# U_I_Meter_Bottom.net
KiCad netlist of a schematic drawn in Altium Designer
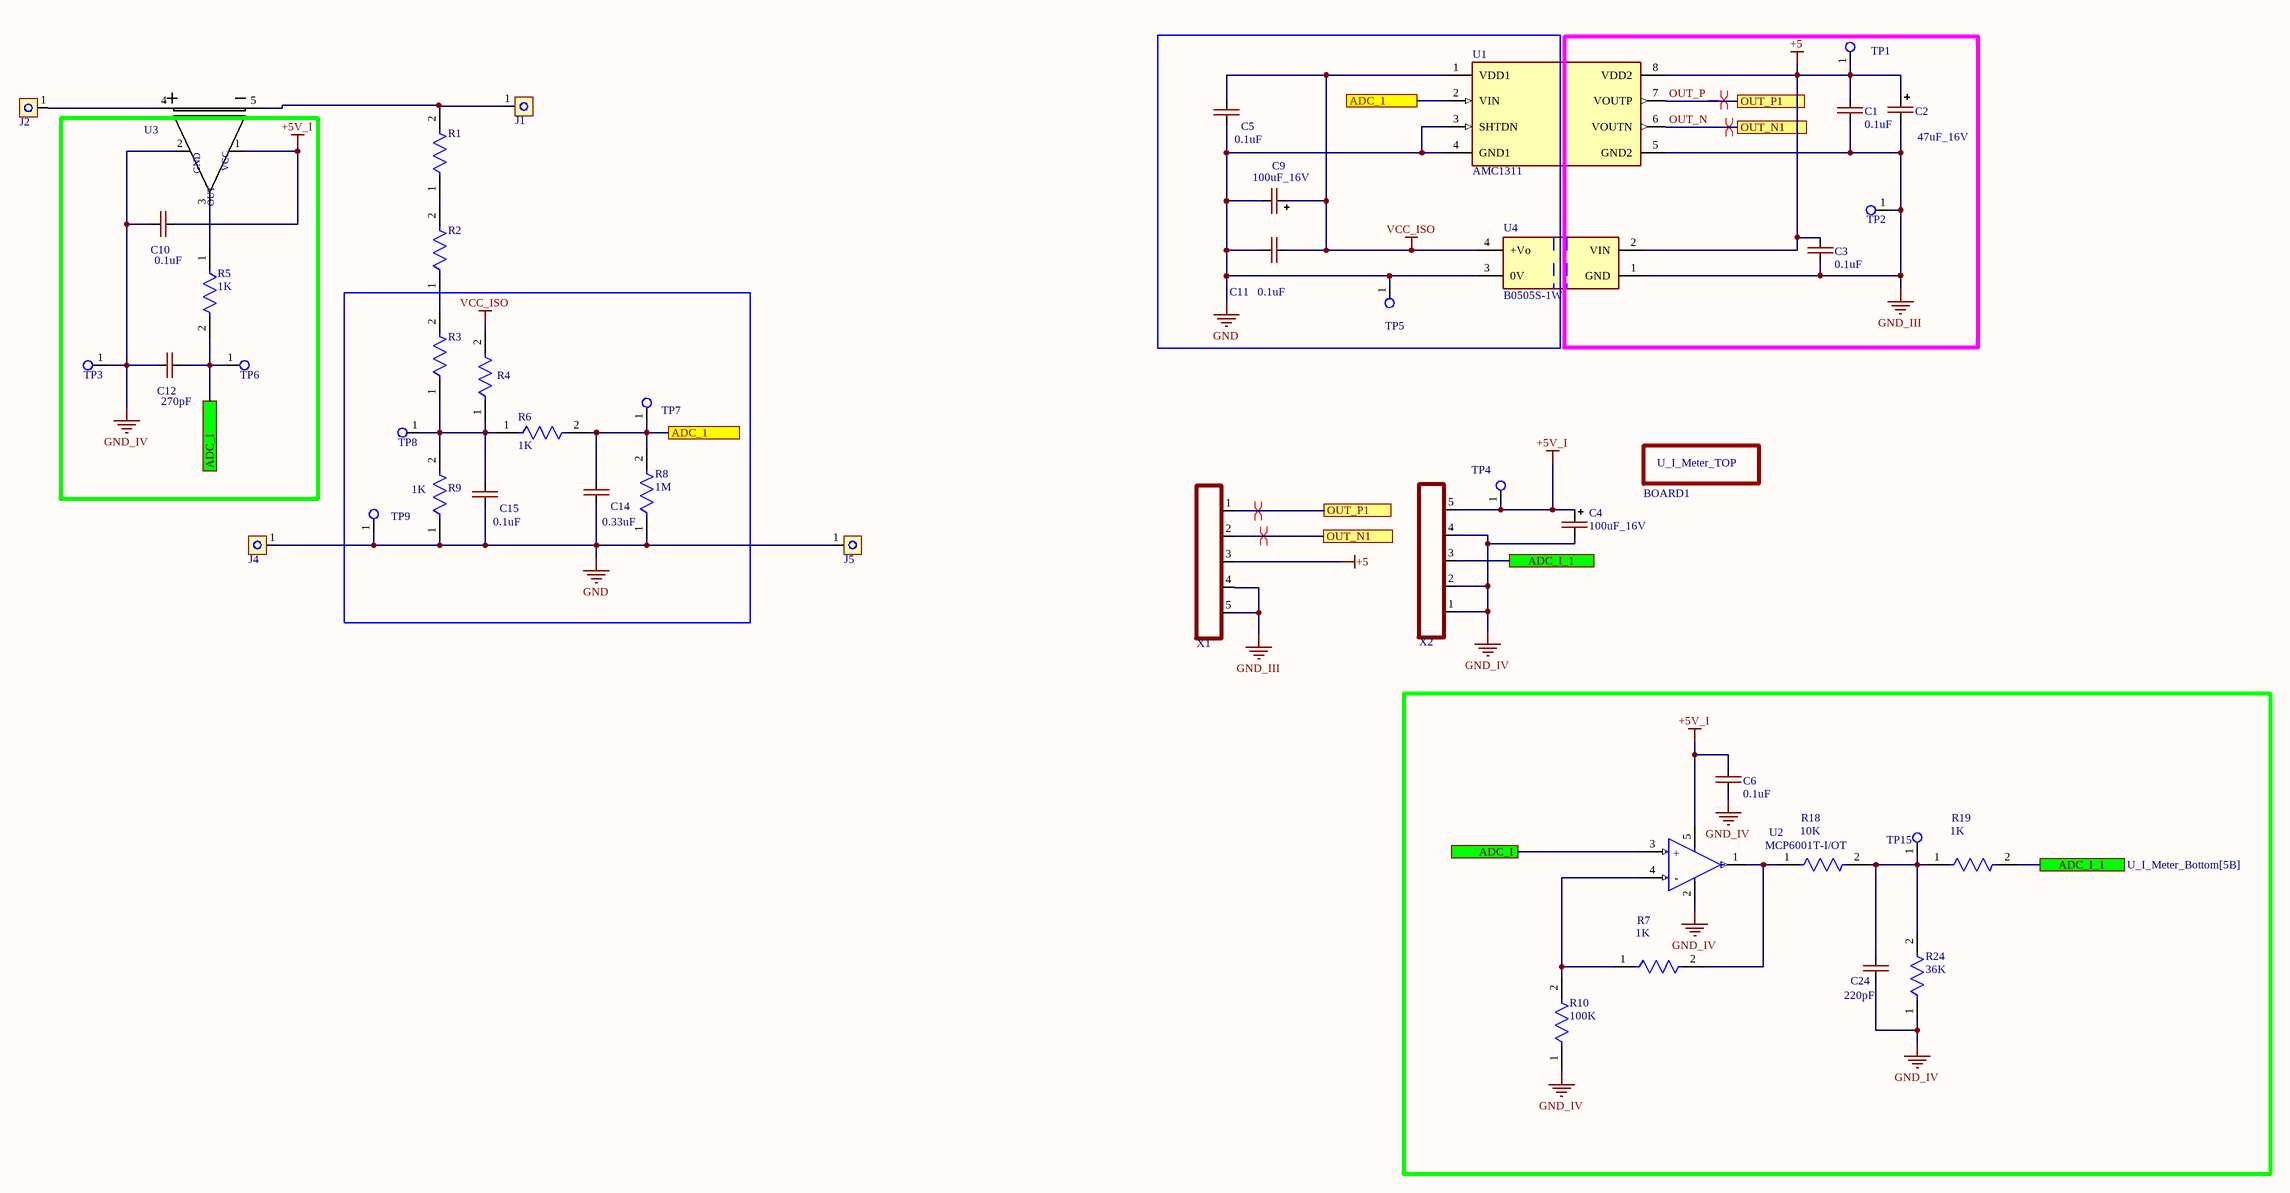
[diagram p0: U_I_Meter_Bottom.SchDoc]

(export (version "E")
  (design (tool "Eeschema 10.0.6"))
  (components
    (comp (ref "BOARD1")
      (value "U_I_Meter_TOP")
      (footprint "U_I_Meter_TOP")
      (libsource (lib "U_I_Meter_TOP") (part "U_I_Meter_TOP"))
    )
    (comp (ref "C1")
      (value "0.1uF")
      (footprint "CAP-0805")
      (libsource (lib "PASSIVE_COMPONENTS") (part "CAP-NON-POLAR"))
    )
    (comp (ref "C2")
      (value "47uF_16V")
      (footprint "CAP-TAN-D")
      (libsource (lib "PASSIVE_COMPONENTS") (part "CAP-POLAR"))
    )
    (comp (ref "C3")
      (value "0.1uF")
      (footprint "CAP-0805")
      (libsource (lib "PASSIVE_COMPONENTS") (part "CAP-NON-POLAR"))
    )
    (comp (ref "C4")
      (value "100uF_16V")
      (footprint "CAP-TAN-D")
      (libsource (lib "PASSIVE_COMPONENTS") (part "CAP_POL_SMD"))
    )
    (comp (ref "C5")
      (value "0.1uF")
      (footprint "CAP-0805")
      (libsource (lib "PASSIVE_COMPONENTS") (part "CAP-NON-POLAR"))
    )
    (comp (ref "C6")
      (value "0.1uF")
      (footprint "CAP-0805")
      (libsource (lib "PASSIVE_COMPONENTS") (part "CAP-NON-POLAR"))
    )
    (comp (ref "C9")
      (value "100uF_16V")
      (footprint "CAP-TAN-D")
      (libsource (lib "PASSIVE_COMPONENTS") (part "CAP_POL_SMD"))
    )
    (comp (ref "C10")
      (value "0.1uF")
      (footprint "CAP-0805")
      (libsource (lib "PASSIVE_COMPONENTS") (part "CAP-NON-POLAR"))
    )
    (comp (ref "C11")
      (value "0.1uF")
      (footprint "CAP-0805")
      (libsource (lib "PASSIVE_COMPONENTS") (part "CAP-NON-POLAR"))
    )
    (comp (ref "C12")
      (value "270pF")
      (footprint "CAP-0805")
      (libsource (lib "PASSIVE_COMPONENTS") (part "CAP-NON-POLAR"))
    )
    (comp (ref "C14")
      (value "0.33uF")
      (footprint "CAP-0805")
      (libsource (lib "PASSIVE_COMPONENTS") (part "CAP-NON-POLAR"))
    )
    (comp (ref "C15")
      (value "0.1uF")
      (footprint "CAP-0805")
      (libsource (lib "PASSIVE_COMPONENTS") (part "CAP-NON-POLAR"))
    )
    (comp (ref "C24")
      (value "220pF")
      (footprint "CAP-0805")
      (libsource (lib "PASSIVE_COMPONENTS") (part "CAP-NON-POLAR"))
    )
    (comp (ref "J1")
      (value "MG_136_HT")
      (footprint "Conn_MEIGAN_MG136HT")
      (libsource (lib "Connectors") (part "Connector_MEIGAN_MG136HT"))
    )
    (comp (ref "J2")
      (value "MG_136_HT")
      (footprint "Conn_MEIGAN_MG136HT")
      (libsource (lib "") (part "Connector_MEIGAN_MG136HT_1"))
    )
    (comp (ref "J4")
      (value "MG_136_HT")
      (footprint "Conn_MEIGAN_MG136HT")
      (libsource (lib "") (part "Connector_MEIGAN_MG136HT_1"))
    )
    (comp (ref "J5")
      (value "MG_136_HT")
      (footprint "Conn_MEIGAN_MG136HT")
      (libsource (lib "Connectors") (part "Connector_MEIGAN_MG136HT"))
    )
    (comp (ref "R1")
      (value "~")
      (footprint "RES-2512")
      (libsource (lib "PASSIVE_COMPONENTS") (part "RES-CONST"))
    )
    (comp (ref "R2")
      (value "~")
      (footprint "RES-2512")
      (libsource (lib "PASSIVE_COMPONENTS") (part "RES-CONST"))
    )
    (comp (ref "R3")
      (value "~")
      (footprint "RES-2512")
      (libsource (lib "PASSIVE_COMPONENTS") (part "RES-CONST"))
    )
    (comp (ref "R4")
      (value "~")
      (footprint "RES-0805")
      (libsource (lib "PASSIVE_COMPONENTS") (part "RES-CONST"))
    )
    (comp (ref "R5")
      (value "1K")
      (footprint "RES-0805")
      (libsource (lib "PASSIVE_COMPONENTS") (part "RES-CONST"))
    )
    (comp (ref "R6")
      (value "1K")
      (footprint "RES-0805")
      (libsource (lib "PASSIVE_COMPONENTS") (part "RES-CONST"))
    )
    (comp (ref "R7")
      (value "1K")
      (footprint "RES-0805")
      (description "10K")
      (libsource (lib "PASSIVE_COMPONENTS") (part "RES-CONST"))
    )
    (comp (ref "R8")
      (value "1M")
      (footprint "RES-0805")
      (libsource (lib "PASSIVE_COMPONENTS") (part "RES-CONST"))
    )
    (comp (ref "R9")
      (value "1K")
      (footprint "RES_SMD_1210_IPC_B")
      (libsource (lib "PASSIVE_COMPONENTS") (part "RES_1210"))
    )
    (comp (ref "R10")
      (value "100K")
      (footprint "RES-0805")
      (libsource (lib "PASSIVE_COMPONENTS") (part "RES-CONST"))
    )
    (comp (ref "R18")
      (value "10K")
      (footprint "RES-0805")
      (libsource (lib "PASSIVE_COMPONENTS") (part "RES-CONST"))
    )
    (comp (ref "R19")
      (value "1K")
      (footprint "RES-0805")
      (description "10K")
      (libsource (lib "PASSIVE_COMPONENTS") (part "RES-CONST"))
    )
    (comp (ref "R24")
      (value "36K")
      (footprint "RES-0805")
      (libsource (lib "PASSIVE_COMPONENTS") (part "RES-CONST"))
    )
    (comp (ref "TP1")
      (value "Test_Point_PCB")
      (footprint "Test_Point")
      (description "Test_Point")
      (libsource (lib "Connectors") (part "TP_PCB?"))
    )
    (comp (ref "TP2")
      (value "Test_Point_PCB")
      (footprint "Test_Point")
      (description "Test_Point")
      (libsource (lib "Connectors") (part "TP_PCB?"))
    )
    (comp (ref "TP3")
      (value "Test_Point_PCB")
      (footprint "Test_Point")
      (description "Test_Point")
      (libsource (lib "Connectors") (part "TP_PCB?"))
    )
    (comp (ref "TP4")
      (value "Test_Point_PCB")
      (footprint "Test_Point")
      (description "Test_Point")
      (libsource (lib "Connectors") (part "TP_PCB?"))
    )
    (comp (ref "TP5")
      (value "Test_Point_PCB")
      (footprint "Pin_Test_Point(Pink)")
      (description "Test_Point")
      (libsource (lib "Connectors") (part "TP_PCB?"))
    )
    (comp (ref "TP6")
      (value "Test_Point_PCB")
      (footprint "Test_Point")
      (description "Test_Point")
      (libsource (lib "Connectors") (part "TP_PCB?"))
    )
    (comp (ref "TP7")
      (value "Test_Point_PCB")
      (footprint "Test_Point")
      (description "Test_Point")
      (libsource (lib "Connectors") (part "TP_PCB?"))
    )
    (comp (ref "TP8")
      (value "Test_Point_PCB")
      (footprint "Test_Point")
      (description "Test_Point")
      (libsource (lib "Connectors") (part "TP_PCB?"))
    )
    (comp (ref "TP9")
      (value "Test_Point_PCB")
      (footprint "Test_Point")
      (description "Test_Point")
      (libsource (lib "Connectors") (part "TP_PCB?"))
    )
    (comp (ref "TP15")
      (value "Test_Point_PCB")
      (footprint "Test_Point")
      (description "Test_Point")
      (libsource (lib "Connectors") (part "TP_PCB?"))
    )
    (comp (ref "U1")
      (value "AMC1311")
      (footprint "FP-DWV0008A-MFG")
      (libsource (lib "Integrated_Circuts") (part "AMC1311"))
    )
    (comp (ref "U2")
      (value "MCP6001T-I/OT")
      (footprint "SOT-23-5")
      (description "IC OPAMP GP 1 CIRCUIT SOT23-5")
      (fields (field (name "VOLTAGE") "6V"))
      (libsource (lib "Integrated_Circuts") (part "MCP6001T"))
    )
    (comp (ref "U3")
      (value "ACS758")
      (footprint "ACS758-100")
      (libsource (lib "Integrated_Circuts") (part "ACS758"))
    )
    (comp (ref "U4")
      (value "B0505S-1W")
      (footprint "B0505S-1W")
      (libsource (lib "Integrated_Circuts") (part "B0505S-1W"))
    )
    (comp (ref "X1")
      (value "CONN-5-PIN")
      (footprint "CONN-PLS-5-2.54mm")
      (libsource (lib "") (part "CONN-5-PIN_1"))
    )
    (comp (ref "X2")
      (value "CONN-5-PIN")
      (footprint "CONN-PLS-5-2.54mm")
      (libsource (lib "PLS-5__") (part "CONN-5-PIN"))
    )
  )
  (nets
    (net (code "1") (name "+5") (class "Default")
      (node (ref "C1") (pin "1") (pinfunction "1_1") (pintype "passive"))
      (node (ref "C2") (pin "1") (pinfunction "+_1") (pintype "passive"))
      (node (ref "C3") (pin "1") (pinfunction "1_1") (pintype "passive"))
      (node (ref "TP1") (pin "1") (pinfunction "G9_1") (pintype "passive"))
      (node (ref "U1") (pin "8") (pinfunction "VDD2_8") (pintype "power_in"))
      (node (ref "U4") (pin "2") (pinfunction "VIN_2") (pintype "power_in"))
      (node (ref "X1") (pin "3") (pinfunction "3_3") (pintype "passive"))
    )
    (net (code "2") (name "+5V_I") (class "Default")
      (node (ref "C10") (pin "2") (pinfunction "2_2") (pintype "passive"))
      (node (ref "C4") (pin "1") (pinfunction "+_1") (pintype "passive"))
      (node (ref "C6") (pin "2") (pinfunction "2_2") (pintype "passive"))
      (node (ref "TP4") (pin "1") (pinfunction "G9_1") (pintype "passive"))
      (node (ref "U2") (pin "5") (pinfunction "VDD_5") (pintype "power_in"))
      (node (ref "U3") (pin "1") (pinfunction "+VCC_1") (pintype "passive"))
      (node (ref "X2") (pin "5") (pinfunction "5_5") (pintype "passive"))
    )
    (net (code "3") (name "/ADC_1") (class "Default")
      (node (ref "C14") (pin "2") (pinfunction "2_2") (pintype "passive"))
      (node (ref "R6") (pin "2") (pinfunction "2_2") (pintype "passive"))
      (node (ref "R8") (pin "2") (pinfunction "2_2") (pintype "passive"))
      (node (ref "TP7") (pin "1") (pinfunction "G9_1") (pintype "passive"))
      (node (ref "U1") (pin "2") (pinfunction "VIN_2") (pintype "input"))
    )
    (net (code "4") (name "/ADC_I") (class "Default")
      (node (ref "C12") (pin "2") (pinfunction "2_2") (pintype "passive"))
      (node (ref "R5") (pin "2") (pinfunction "2_2") (pintype "passive"))
      (node (ref "TP6") (pin "1") (pinfunction "G9_1") (pintype "passive"))
      (node (ref "U2") (pin "3") (pinfunction "VIN+_3") (pintype "input"))
    )
    (net (code "5") (name "/ADC_I_1") (class "Default")
      (node (ref "R19") (pin "2") (pinfunction "2_2") (pintype "passive"))
      (node (ref "X2") (pin "3") (pinfunction "3_3") (pintype "passive"))
    )
    (net (code "6") (name "/OUT_N") (class "Default")
      (node (ref "U1") (pin "6") (pinfunction "VOUTN_6") (pintype "output"))
      (node (ref "X1") (pin "2") (pinfunction "2_2") (pintype "passive"))
    )
    (net (code "7") (name "/OUT_P") (class "Default")
      (node (ref "U1") (pin "7") (pinfunction "VOUTP_7") (pintype "output"))
      (node (ref "X1") (pin "1") (pinfunction "1_1") (pintype "passive"))
    )
    (net (code "8") (name "GND") (class "Default")
      (node (ref "C11") (pin "2") (pinfunction "2_2") (pintype "passive"))
      (node (ref "C14") (pin "1") (pinfunction "1_1") (pintype "passive"))
      (node (ref "C15") (pin "1") (pinfunction "1_1") (pintype "passive"))
      (node (ref "C5") (pin "1") (pinfunction "1_1") (pintype "passive"))
      (node (ref "C9") (pin "2") (pinfunction "-_2") (pintype "passive"))
      (node (ref "J4") (pin "1") (pinfunction "17_1") (pintype "passive"))
      (node (ref "J5") (pin "1") (pinfunction "17_1") (pintype "passive"))
      (node (ref "R8") (pin "1") (pinfunction "1_1") (pintype "passive"))
      (node (ref "R9") (pin "1") (pinfunction "1_1") (pintype "passive"))
      (node (ref "TP5") (pin "1") (pinfunction "G9_1") (pintype "passive"))
      (node (ref "TP9") (pin "1") (pinfunction "G9_1") (pintype "passive"))
      (node (ref "U1") (pin "3") (pinfunction "SHTDN_3") (pintype "input"))
      (node (ref "U1") (pin "4") (pinfunction "GND1_4") (pintype "power_in"))
      (node (ref "U4") (pin "3") (pinfunction "0V_3") (pintype "power_in"))
    )
    (net (code "9") (name "GND_III") (class "Default")
      (node (ref "C1") (pin "2") (pinfunction "2_2") (pintype "passive"))
      (node (ref "C2") (pin "2") (pinfunction "-_2") (pintype "passive"))
      (node (ref "C3") (pin "2") (pinfunction "2_2") (pintype "passive"))
      (node (ref "TP2") (pin "1") (pinfunction "G9_1") (pintype "passive"))
      (node (ref "U1") (pin "5") (pinfunction "GND2_5") (pintype "power_in"))
      (node (ref "U4") (pin "1") (pinfunction "GND_1") (pintype "power_in"))
      (node (ref "X1") (pin "4") (pinfunction "4_4") (pintype "passive"))
      (node (ref "X1") (pin "5") (pinfunction "5_5") (pintype "passive"))
    )
    (net (code "10") (name "GND_IV") (class "Default")
      (node (ref "C10") (pin "1") (pinfunction "1_1") (pintype "passive"))
      (node (ref "C12") (pin "1") (pinfunction "1_1") (pintype "passive"))
      (node (ref "C24") (pin "1") (pinfunction "1_1") (pintype "passive"))
      (node (ref "C4") (pin "2") (pinfunction "-_2") (pintype "passive"))
      (node (ref "C6") (pin "1") (pinfunction "1_1") (pintype "passive"))
      (node (ref "R10") (pin "1") (pinfunction "1_1") (pintype "passive"))
      (node (ref "R24") (pin "1") (pinfunction "1_1") (pintype "passive"))
      (node (ref "TP3") (pin "1") (pinfunction "G9_1") (pintype "passive"))
      (node (ref "U2") (pin "2") (pinfunction "VSS_2") (pintype "power_in"))
      (node (ref "U3") (pin "2") (pinfunction "GND_2") (pintype "passive"))
      (node (ref "X2") (pin "1") (pinfunction "1_1") (pintype "passive"))
      (node (ref "X2") (pin "2") (pinfunction "2_2") (pintype "passive"))
      (node (ref "X2") (pin "4") (pinfunction "4_4") (pintype "passive"))
    )
    (net (code "11") (name "Net-(J1-17)") (class "Default")
      (node (ref "J1") (pin "1") (pinfunction "17_1") (pintype "passive"))
      (node (ref "R1") (pin "2") (pinfunction "2_2") (pintype "passive"))
      (node (ref "U3") (pin "5") (pinfunction "-IP_5") (pintype "passive"))
    )
    (net (code "12") (name "Net-(J2-17)") (class "Default")
      (node (ref "J2") (pin "1") (pinfunction "17_1") (pintype "passive"))
      (node (ref "U3") (pin "4") (pinfunction "+IP_4") (pintype "passive"))
    )
    (net (code "13") (name "Net-(R1-Pad1)") (class "Default")
      (node (ref "R1") (pin "1") (pinfunction "1_1") (pintype "passive"))
      (node (ref "R2") (pin "2") (pinfunction "2_2") (pintype "passive"))
    )
    (net (code "14") (name "Net-(R2-Pad1)") (class "Default")
      (node (ref "R2") (pin "1") (pinfunction "1_1") (pintype "passive"))
      (node (ref "R3") (pin "2") (pinfunction "2_2") (pintype "passive"))
    )
    (net (code "15") (name "Net-(TP8-G9)") (class "Default")
      (node (ref "C15") (pin "2") (pinfunction "2_2") (pintype "passive"))
      (node (ref "R3") (pin "1") (pinfunction "1_1") (pintype "passive"))
      (node (ref "R4") (pin "1") (pinfunction "1_1") (pintype "passive"))
      (node (ref "R6") (pin "1") (pinfunction "1_1") (pintype "passive"))
      (node (ref "R9") (pin "2") (pinfunction "2_2") (pintype "passive"))
      (node (ref "TP8") (pin "1") (pinfunction "G9_1") (pintype "passive"))
    )
    (net (code "16") (name "Net-(TP15-G9)") (class "Default")
      (node (ref "C24") (pin "2") (pinfunction "2_2") (pintype "passive"))
      (node (ref "R18") (pin "2") (pinfunction "2_2") (pintype "passive"))
      (node (ref "R19") (pin "1") (pinfunction "1_1") (pintype "passive"))
      (node (ref "R24") (pin "2") (pinfunction "2_2") (pintype "passive"))
      (node (ref "TP15") (pin "1") (pinfunction "G9_1") (pintype "passive"))
    )
    (net (code "17") (name "Net-(U2-VIN-)") (class "Default")
      (node (ref "R10") (pin "2") (pinfunction "2_2") (pintype "passive"))
      (node (ref "R7") (pin "1") (pinfunction "1_1") (pintype "passive"))
      (node (ref "U2") (pin "4") (pinfunction "VIN-_4") (pintype "input"))
    )
    (net (code "18") (name "Net-(U2-VOUT)") (class "Default")
      (node (ref "R18") (pin "1") (pinfunction "1_1") (pintype "passive"))
      (node (ref "R7") (pin "2") (pinfunction "2_2") (pintype "passive"))
      (node (ref "U2") (pin "1") (pinfunction "VOUT_1") (pintype "output"))
    )
    (net (code "19") (name "Net-(U3-OUT)") (class "Default")
      (node (ref "R5") (pin "1") (pinfunction "1_1") (pintype "passive"))
      (node (ref "U3") (pin "3") (pinfunction "OUT_3") (pintype "passive"))
    )
    (net (code "20") (name "VCC_ISO") (class "Default")
      (node (ref "C11") (pin "1") (pinfunction "1_1") (pintype "passive"))
      (node (ref "C5") (pin "2") (pinfunction "2_2") (pintype "passive"))
      (node (ref "C9") (pin "1") (pinfunction "+_1") (pintype "passive"))
      (node (ref "R4") (pin "2") (pinfunction "2_2") (pintype "passive"))
      (node (ref "U1") (pin "1") (pinfunction "VDD1_1") (pintype "power_in"))
      (node (ref "U4") (pin "4") (pinfunction "+Vo_4") (pintype "power_in"))
    )
  )
)
